# 03_Schematic.net
KiCad netlist of a schematic drawn in Altium Designer
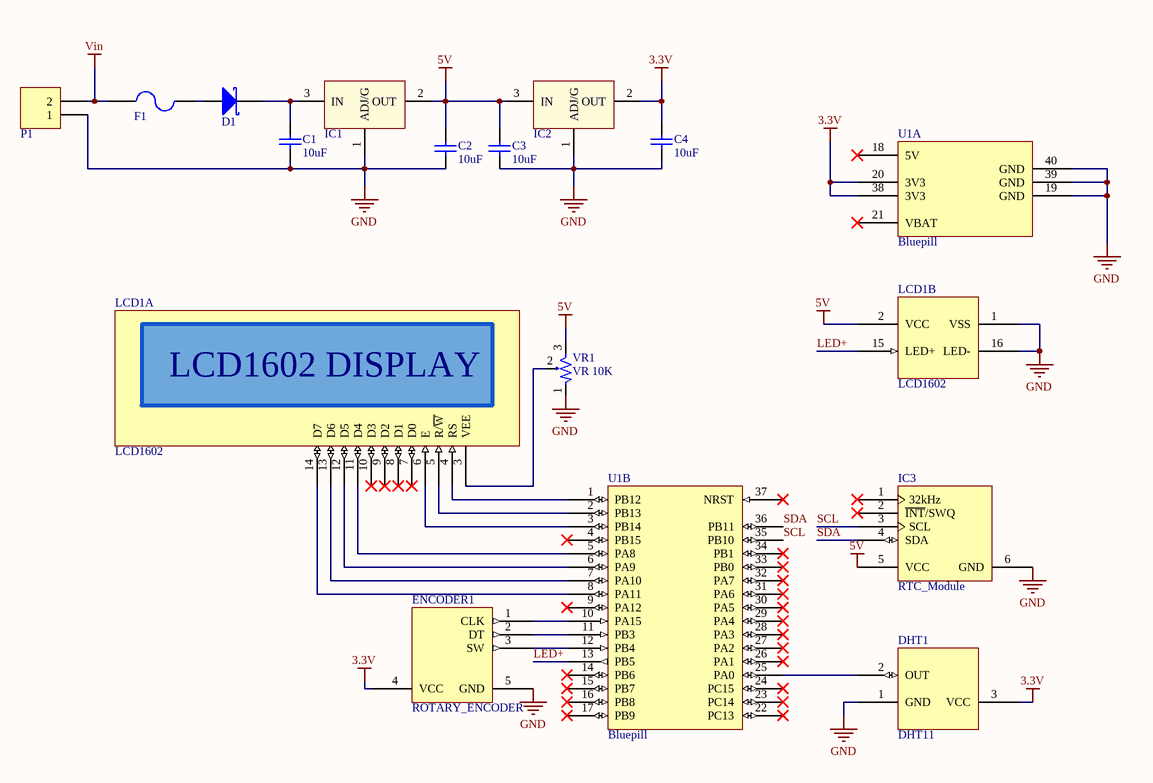
[diagram p0: 03_Schematic.SchDoc]

(export (version "E")
  (design (tool "Eeschema 10.0.6"))
  (components
    (comp (ref "C1")
      (value "10uF")
      (footprint "CAP-SM-0805")
      (description "Capacitor")
      (fields (field (name "Comment") "Cap Non-Pol SMD"))
      (libsource (lib "PIF_Library") (part "Cap Non-Pol SMD"))
    )
    (comp (ref "C2")
      (value "10uF")
      (footprint "CAP-SM-0805")
      (description "Capacitor")
      (fields (field (name "Comment") "Cap Non-Pol SMD"))
      (libsource (lib "PIF_Library") (part "Cap Non-Pol SMD"))
    )
    (comp (ref "C3")
      (value "10uF")
      (footprint "CAP-SM-0805")
      (description "Capacitor")
      (fields (field (name "Comment") "Cap Non-Pol SMD"))
      (libsource (lib "PIF_Library") (part "Cap Non-Pol SMD"))
    )
    (comp (ref "C4")
      (value "10uF")
      (footprint "CAP-SM-0805")
      (description "Capacitor")
      (fields (field (name "Comment") "Cap Non-Pol SMD"))
      (libsource (lib "PIF_Library") (part "Cap Non-Pol SMD"))
    )
    (comp (ref "D1")
      (value "D Schottky")
      (footprint "SS34")
      (description "Schottky Diode")
      (fields (field (name "PUBLISHER") "Altium Limited"))
      (libsource (lib "PIF_Library") (part "D Schottky"))
    )
    (comp (ref "DHT1")
      (value "DHT11")
      (footprint "DHT11")
      (description "Temperature Humidity Sensor 16bi\r\nHumidity, Temperature Digital ±5% RH Through Hole")
      (fields (field (name "MANUFACTURER") "UNIVERSAL-SOLDER Electronics Ltd"))
      (libsource (lib "LibraryOfficial_INTEGRATEDLib_Hnit_20230222") (part "DHT11"))
    )
    (comp (ref "ENCODER1")
      (value "ROTARY_ENCODER")
      (footprint "ROTARY_ENCODER")
      (description "4 Position Wire to Board Terminal Block Horizontal with Board 0.197\" (5.00mm) Through Hole")
      (fields (field (name "MANUFACTURER") "Amphenol Anytek") (field (name "VOLTAGE") "300 V"))
      (libsource (lib "LibraryOfficial_INTEGRATEDLib_Hnit_20230222") (part "ROTARY_ENCODER"))
    )
    (comp (ref "F1") (value "Fuse") (footprint "FUSE SMD") (libsource (lib "PIF_Library") (part "Fuse")))
    (comp (ref "IC1")
      (value "LM1117")
      (footprint "SOT223-4N")
      (description "Available in 1.8V, 2.5V, 2.85V, 3.3V, 5V, and  Adjustable Versions")
      (libsource (lib "PIF_Library") (part "LM1117"))
    )
    (comp (ref "IC2")
      (value "LM1117")
      (footprint "SOT223-4N")
      (description "Available in 1.8V, 2.5V, 2.85V, 3.3V, 5V, and  Adjustable Versions")
      (libsource (lib "PIF_Library") (part "LM1117"))
    )
    (comp (ref "IC3")
      (value "RTC_Module")
      (footprint "DS3231_PINOUT_Module")
      (description "RTC MODULE CLK/CALENDAR I2C 16SOIC")
      (fields (field (name "MANUFACTURER") "Seeed Technology Co., Ltd"))
      (libsource (lib "LibraryOfficial_INTEGRATEDLib_Hnit_20230222") (part "DS3231"))
    )
    (comp (ref "LCD1")
      (value "LCD1602")
      (footprint "LCD1602")
      (libsource (lib "LibraryOfficial_INTEGRATEDLib_Hnit_20230222") (part "LCD1602"))
    )
    (comp (ref "P1")
      (value "Domino 2")
      (footprint "DOMINO SMALL 2")
      (description "Domino, 2-Pin")
      (fields (field (name "PUBLISHER") "Altium Limited"))
      (libsource (lib "PIF_Library") (part "Domino 2"))
    )
    (comp (ref "U1")
      (value "Bluepill")
      (footprint "STM32F103C8T6_PINOUT_Bluepill")
      (fields (field (name "MANUFACTURER") "STMicroelectronics"))
      (libsource (lib "LibraryOfficial_INTEGRATEDLib_Hnit_20230222") (part "STM32F103C8T6"))
    )
    (comp (ref "VR1")
      (value "VR 10K")
      (footprint "Varistor 1")
      (description "Var Resistor")
      (fields (field (name "Comment") "10K"))
      (libsource (lib "PIF_Library") (part "Var Resistor"))
    )
  )
  (nets
    (net (code "1") (name "/LED+") (class "Default")
      (node (ref "LCD1") (pin "15") (pinfunction "LED+_15") (pintype "power_in"))
      (node (ref "U1") (pin "13") (pinfunction "PB5_13") (pintype "output"))
    )
    (net (code "2") (name "/SCL") (class "Default")
      (node (ref "IC3") (pin "3") (pinfunction "SCL_3") (pintype "passive"))
      (node (ref "U1") (pin "35") (pinfunction "PB10_35") (pintype "bidirectional"))
    )
    (net (code "3") (name "/SDA") (class "Default")
      (node (ref "IC3") (pin "4") (pinfunction "SDA_4") (pintype "bidirectional"))
      (node (ref "U1") (pin "36") (pinfunction "PB11_36") (pintype "bidirectional"))
    )
    (net (code "4") (name "3.3V") (class "Default")
      (node (ref "C4") (pin "2") (pinfunction "2_2") (pintype "passive"))
      (node (ref "DHT1") (pin "3") (pinfunction "VCC_3") (pintype "power_in"))
      (node (ref "ENCODER1") (pin "4") (pinfunction "VCC_4") (pintype "power_in"))
      (node (ref "IC2") (pin "2") (pinfunction "OUT_2") (pintype "passive"))
      (node (ref "U1") (pin "20") (pinfunction "3V3_20") (pintype "power_in"))
      (node (ref "U1") (pin "38") (pinfunction "3V3_38") (pintype "power_in"))
    )
    (net (code "5") (name "5V") (class "Default")
      (node (ref "C2") (pin "2") (pinfunction "2_2") (pintype "passive"))
      (node (ref "C3") (pin "2") (pinfunction "2_2") (pintype "passive"))
      (node (ref "IC1") (pin "2") (pinfunction "OUT_2") (pintype "passive"))
      (node (ref "IC2") (pin "3") (pinfunction "IN_3") (pintype "passive"))
      (node (ref "IC3") (pin "5") (pinfunction "VCC_5") (pintype "power_in"))
      (node (ref "LCD1") (pin "2") (pinfunction "VCC_2") (pintype "power_in"))
      (node (ref "VR1") (pin "3") (pinfunction "3_3") (pintype "passive"))
    )
    (net (code "6") (name "GND") (class "Default")
      (node (ref "C1") (pin "1") (pinfunction "1_1") (pintype "passive"))
      (node (ref "C2") (pin "1") (pinfunction "1_1") (pintype "passive"))
      (node (ref "C3") (pin "1") (pinfunction "1_1") (pintype "passive"))
      (node (ref "C4") (pin "1") (pinfunction "1_1") (pintype "passive"))
      (node (ref "DHT1") (pin "1") (pinfunction "GND_1") (pintype "power_in"))
      (node (ref "ENCODER1") (pin "5") (pinfunction "GND_5") (pintype "power_in"))
      (node (ref "IC1") (pin "1") (pinfunction "ADJ/G_1") (pintype "passive"))
      (node (ref "IC2") (pin "1") (pinfunction "ADJ/G_1") (pintype "passive"))
      (node (ref "IC3") (pin "6") (pinfunction "GND_6") (pintype "power_in"))
      (node (ref "LCD1") (pin "1") (pinfunction "VSS_1") (pintype "power_in"))
      (node (ref "LCD1") (pin "16") (pinfunction "LED-_16") (pintype "power_in"))
      (node (ref "P1") (pin "1") (pinfunction "1_1") (pintype "passive"))
      (node (ref "U1") (pin "19") (pinfunction "GND_19") (pintype "power_in"))
      (node (ref "U1") (pin "39") (pinfunction "GND_39") (pintype "power_in"))
      (node (ref "U1") (pin "40") (pinfunction "GND_40") (pintype "power_in"))
      (node (ref "VR1") (pin "1") (pinfunction "1_1") (pintype "passive"))
    )
    (net (code "7") (name "Net-(D1-A)") (class "Default")
      (node (ref "D1") (pin "1") (pinfunction "A_1") (pintype "passive"))
      (node (ref "F1") (pin "2") (pinfunction "2_2") (pintype "passive"))
    )
    (net (code "8") (name "Net-(D1-K)") (class "Default")
      (node (ref "C1") (pin "2") (pinfunction "2_2") (pintype "passive"))
      (node (ref "D1") (pin "2") (pinfunction "K_2") (pintype "passive"))
      (node (ref "IC1") (pin "3") (pinfunction "IN_3") (pintype "passive"))
    )
    (net (code "9") (name "Net-(DHT1-OUT)") (class "Default")
      (node (ref "DHT1") (pin "2") (pinfunction "OUT_2") (pintype "bidirectional"))
      (node (ref "U1") (pin "25") (pinfunction "PA0_25") (pintype "bidirectional"))
    )
    (net (code "10") (name "Net-(ENCODER1-CLK)") (class "Default")
      (node (ref "ENCODER1") (pin "1") (pinfunction "CLK_1") (pintype "output"))
      (node (ref "U1") (pin "10") (pinfunction "PA15_10") (pintype "input"))
    )
    (net (code "11") (name "Net-(ENCODER1-DT)") (class "Default")
      (node (ref "ENCODER1") (pin "2") (pinfunction "DT_2") (pintype "output"))
      (node (ref "U1") (pin "11") (pinfunction "PB3_11") (pintype "input"))
    )
    (net (code "12") (name "Net-(ENCODER1-SW)") (class "Default")
      (node (ref "ENCODER1") (pin "3") (pinfunction "SW_3") (pintype "output"))
      (node (ref "U1") (pin "12") (pinfunction "PB4_12") (pintype "input"))
    )
    (net (code "13") (name "Net-(LCD1A-D4)") (class "Default")
      (node (ref "LCD1") (pin "11") (pinfunction "D4_11") (pintype "bidirectional"))
      (node (ref "U1") (pin "5") (pinfunction "PA8_5") (pintype "bidirectional"))
    )
    (net (code "14") (name "Net-(LCD1A-D5)") (class "Default")
      (node (ref "LCD1") (pin "12") (pinfunction "D5_12") (pintype "bidirectional"))
      (node (ref "U1") (pin "6") (pinfunction "PA9_6") (pintype "bidirectional"))
    )
    (net (code "15") (name "Net-(LCD1A-D6)") (class "Default")
      (node (ref "LCD1") (pin "13") (pinfunction "D6_13") (pintype "bidirectional"))
      (node (ref "U1") (pin "7") (pinfunction "PA10_7") (pintype "bidirectional"))
    )
    (net (code "16") (name "Net-(LCD1A-D7)") (class "Default")
      (node (ref "LCD1") (pin "14") (pinfunction "D7_14") (pintype "bidirectional"))
      (node (ref "U1") (pin "8") (pinfunction "PA11_8") (pintype "bidirectional"))
    )
    (net (code "17") (name "Net-(LCD1A-E)") (class "Default")
      (node (ref "LCD1") (pin "6") (pinfunction "E_6") (pintype "input"))
      (node (ref "U1") (pin "3") (pinfunction "PB14_3") (pintype "bidirectional"))
    )
    (net (code "18") (name "Net-(LCD1A-RS)") (class "Default")
      (node (ref "LCD1") (pin "4") (pinfunction "RS_4") (pintype "input"))
      (node (ref "U1") (pin "1") (pinfunction "PB12_1") (pintype "bidirectional"))
    )
    (net (code "19") (name "Net-(LCD1A-R{slash}~{W})") (class "Default")
      (node (ref "LCD1") (pin "5") (pinfunction "R/~{W}_5") (pintype "input"))
      (node (ref "U1") (pin "2") (pinfunction "PB13_2") (pintype "bidirectional"))
    )
    (net (code "20") (name "Net-(LCD1A-VEE)") (class "Default")
      (node (ref "LCD1") (pin "3") (pinfunction "VEE_3") (pintype "power_in"))
      (node (ref "VR1") (pin "2") (pinfunction "2_2") (pintype "passive"))
    )
    (net (code "21") (name "Vin") (class "Default")
      (node (ref "F1") (pin "1") (pinfunction "1_1") (pintype "passive"))
      (node (ref "P1") (pin "2") (pinfunction "2_2") (pintype "passive"))
    )
    (net (code "22") (name "unconnected-(IC3-32kHz-Pad1)") (class "Default")
      (node (ref "IC3") (pin "1") (pinfunction "32kHz_1") (pintype "passive+no_connect"))
    )
    (net (code "23") (name "unconnected-(IC3-~{INT}{slash}SWQ-Pad2)") (class "Default")
      (node (ref "IC3") (pin "2") (pinfunction "~{INT}/SWQ_2") (pintype "passive+no_connect"))
    )
    (net (code "24") (name "unconnected-(LCD1A-D0-Pad7)") (class "Default")
      (node (ref "LCD1") (pin "7") (pinfunction "D0_7") (pintype "bidirectional+no_connect"))
    )
    (net (code "25") (name "unconnected-(LCD1A-D1-Pad8)") (class "Default")
      (node (ref "LCD1") (pin "8") (pinfunction "D1_8") (pintype "bidirectional+no_connect"))
    )
    (net (code "26") (name "unconnected-(LCD1A-D2-Pad9)") (class "Default")
      (node (ref "LCD1") (pin "9") (pinfunction "D2_9") (pintype "bidirectional+no_connect"))
    )
    (net (code "27") (name "unconnected-(LCD1A-D3-Pad10)") (class "Default")
      (node (ref "LCD1") (pin "10") (pinfunction "D3_10") (pintype "bidirectional+no_connect"))
    )
    (net (code "28") (name "unconnected-(U1A-5V-Pad18)") (class "Default")
      (node (ref "U1") (pin "18") (pinfunction "5V_18") (pintype "power_in+no_connect"))
    )
    (net (code "29") (name "unconnected-(U1A-VBAT-Pad21)") (class "Default")
      (node (ref "U1") (pin "21") (pinfunction "VBAT_21") (pintype "power_in+no_connect"))
    )
    (net (code "30") (name "unconnected-(U1B-NRST-Pad37)") (class "Default")
      (node (ref "U1") (pin "37") (pinfunction "NRST_37") (pintype "input+no_connect"))
    )
    (net (code "31") (name "unconnected-(U1B-PA1-Pad26)") (class "Default")
      (node (ref "U1") (pin "26") (pinfunction "PA1_26") (pintype "bidirectional+no_connect"))
    )
    (net (code "32") (name "unconnected-(U1B-PA2-Pad27)") (class "Default")
      (node (ref "U1") (pin "27") (pinfunction "PA2_27") (pintype "bidirectional+no_connect"))
    )
    (net (code "33") (name "unconnected-(U1B-PA3-Pad28)") (class "Default")
      (node (ref "U1") (pin "28") (pinfunction "PA3_28") (pintype "bidirectional+no_connect"))
    )
    (net (code "34") (name "unconnected-(U1B-PA4-Pad29)") (class "Default")
      (node (ref "U1") (pin "29") (pinfunction "PA4_29") (pintype "bidirectional+no_connect"))
    )
    (net (code "35") (name "unconnected-(U1B-PA5-Pad30)") (class "Default")
      (node (ref "U1") (pin "30") (pinfunction "PA5_30") (pintype "bidirectional+no_connect"))
    )
    (net (code "36") (name "unconnected-(U1B-PA6-Pad31)") (class "Default")
      (node (ref "U1") (pin "31") (pinfunction "PA6_31") (pintype "bidirectional+no_connect"))
    )
    (net (code "37") (name "unconnected-(U1B-PA7-Pad32)") (class "Default")
      (node (ref "U1") (pin "32") (pinfunction "PA7_32") (pintype "bidirectional+no_connect"))
    )
    (net (code "38") (name "unconnected-(U1B-PA12-Pad9)") (class "Default")
      (node (ref "U1") (pin "9") (pinfunction "PA12_9") (pintype "bidirectional+no_connect"))
    )
    (net (code "39") (name "unconnected-(U1B-PB0-Pad33)") (class "Default")
      (node (ref "U1") (pin "33") (pinfunction "PB0_33") (pintype "bidirectional+no_connect"))
    )
    (net (code "40") (name "unconnected-(U1B-PB1-Pad34)") (class "Default")
      (node (ref "U1") (pin "34") (pinfunction "PB1_34") (pintype "bidirectional+no_connect"))
    )
    (net (code "41") (name "unconnected-(U1B-PB6-Pad14)") (class "Default")
      (node (ref "U1") (pin "14") (pinfunction "PB6_14") (pintype "bidirectional+no_connect"))
    )
    (net (code "42") (name "unconnected-(U1B-PB7-Pad15)") (class "Default")
      (node (ref "U1") (pin "15") (pinfunction "PB7_15") (pintype "bidirectional+no_connect"))
    )
    (net (code "43") (name "unconnected-(U1B-PB8-Pad16)") (class "Default")
      (node (ref "U1") (pin "16") (pinfunction "PB8_16") (pintype "bidirectional+no_connect"))
    )
    (net (code "44") (name "unconnected-(U1B-PB9-Pad17)") (class "Default")
      (node (ref "U1") (pin "17") (pinfunction "PB9_17") (pintype "bidirectional+no_connect"))
    )
    (net (code "45") (name "unconnected-(U1B-PB15-Pad4)") (class "Default")
      (node (ref "U1") (pin "4") (pinfunction "PB15_4") (pintype "bidirectional+no_connect"))
    )
    (net (code "46") (name "unconnected-(U1B-PC13-Pad22)") (class "Default")
      (node (ref "U1") (pin "22") (pinfunction "PC13_22") (pintype "bidirectional+no_connect"))
    )
    (net (code "47") (name "unconnected-(U1B-PC14-Pad23)") (class "Default")
      (node (ref "U1") (pin "23") (pinfunction "PC14_23") (pintype "bidirectional+no_connect"))
    )
    (net (code "48") (name "unconnected-(U1B-PC15-Pad24)") (class "Default")
      (node (ref "U1") (pin "24") (pinfunction "PC15_24") (pintype "bidirectional+no_connect"))
    )
  )
)
